# Servo.net
KiCad netlist of a schematic drawn in Altium Designer
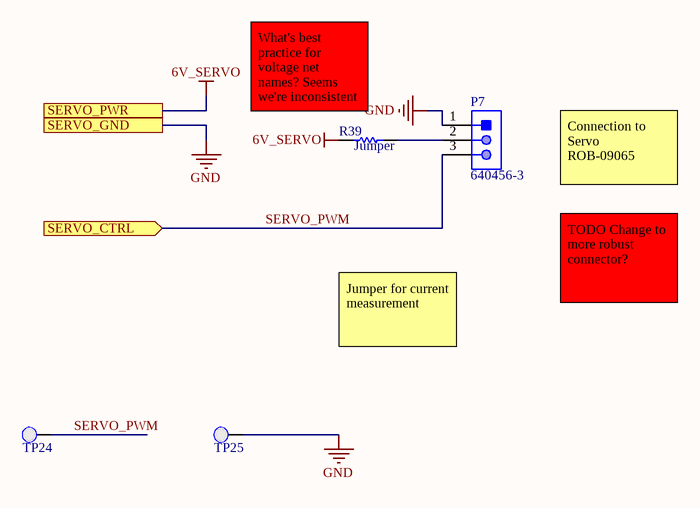
[diagram p0: Servo.SchDoc]

(export (version "E")
  (design (tool "Eeschema 10.0.6"))
  (components
    (comp (ref "P7")
      (value "640456-3")
      (footprint "TECO-640456-3")
      (description "Male Header, Pitch 2.54 mm, 1 x 3 Position, Height 10.03 mm, Tail Length 3.56 mm, -55 to 105 degC")
      (fields (field (name "MANUFACTURER") "TE Connectivity"))
      (libsource (lib "Altium Content Vault") (part "CN-1P-M-R3"))
    )
    (comp (ref "R39")
      (value "Jumper")
      (footprint "RESC0603(1608)_N")
      (description "Jumper 0603 (1608 Metric)")
      (fields (field (name "POWER") "None"))
      (libsource (lib "Altium Content Vault") (part "RES"))
    )
    (comp (ref "TP24")
      (value "0.1\" Pad")
      (footprint "PCBComponent")
      (libsource (lib "Components - 12.02.20 - 18.05") (part "0.1{dblquote} Pad-A.4"))
    )
    (comp (ref "TP25")
      (value "0.1\" Pad")
      (footprint "PCBComponent")
      (libsource (lib "Components - 12.02.20 - 18.05") (part "0.1{dblquote} Pad-A.4"))
    )
  )
  (nets
    (net (code "1") (name "/SERVO_PWM") (class "Default")
      (node (ref "P7") (pin "3") (pinfunction "3_3") (pintype "passive"))
      (node (ref "TP24") (pin "1") (pinfunction "PAD_1") (pintype "passive"))
    )
    (net (code "2") (name "6V_SERVO") (class "Default")
      (node (ref "R39") (pin "1") (pinfunction "1_1") (pintype "passive"))
    )
    (net (code "3") (name "GND") (class "Default")
      (node (ref "P7") (pin "1") (pinfunction "1_1") (pintype "passive"))
      (node (ref "TP25") (pin "1") (pinfunction "PAD_1") (pintype "passive"))
    )
    (net (code "4") (name "Net-(P7-Pad2)") (class "Default")
      (node (ref "P7") (pin "2") (pinfunction "2_2") (pintype "passive"))
      (node (ref "R39") (pin "2") (pinfunction "2_2") (pintype "passive"))
    )
  )
)
